# ppc_extbus.net
KiCad netlist of a schematic drawn in Altium Designer
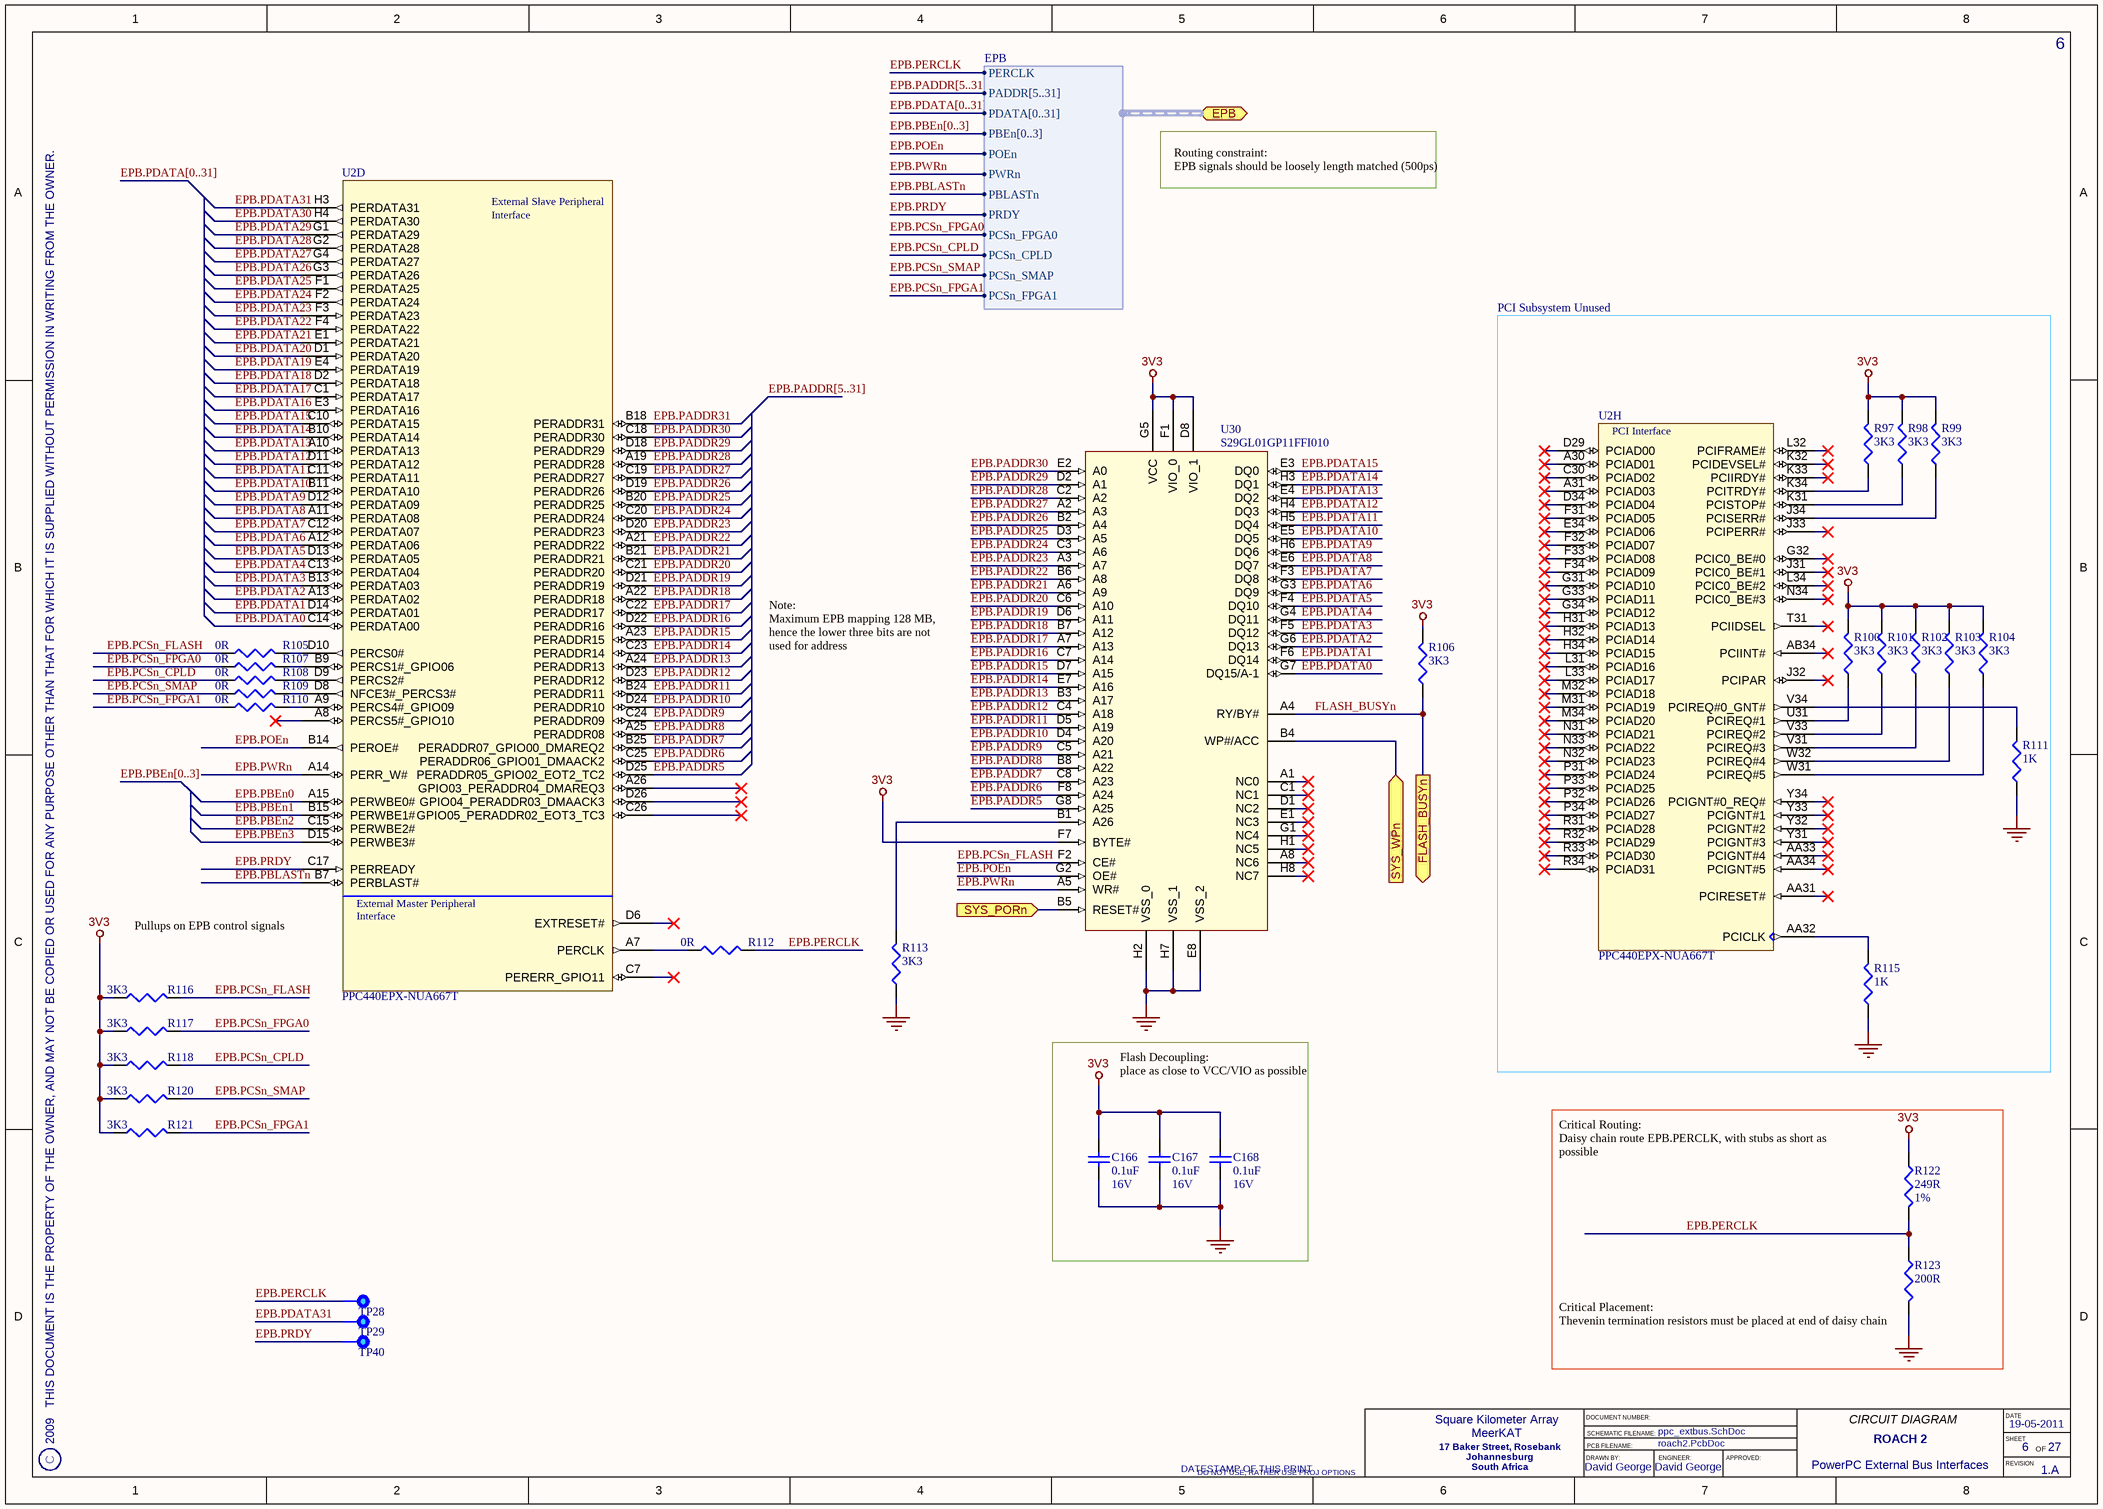
[diagram p0: ppc_extbus.SchDoc]

(export (version "E")
  (design (tool "Eeschema 10.0.6"))
  (components
    (comp (ref "C166")
      (value "0.1uF")
      (footprint "CAPC1005X60L")
      (description "0.1uF, Ceramic Capacitor")
      (fields
        (field (name "MANUFACTURER") "VENKEL")
        (field (name "PARTNUM") "C0402X7R160-104KN")
        (field (name "RATING") "16V")
      )
      (libsource (lib "altium_db") (part "CapStd"))
    )
    (comp (ref "C167")
      (value "0.1uF")
      (footprint "CAPC1005X60L")
      (description "0.1uF, Ceramic Capacitor")
      (fields
        (field (name "MANUFACTURER") "VENKEL")
        (field (name "PARTNUM") "C0402X7R160-104KN")
        (field (name "RATING") "16V")
      )
      (libsource (lib "altium_db") (part "CapStd"))
    )
    (comp (ref "C168")
      (value "0.1uF")
      (footprint "CAPC1005X60L")
      (description "0.1uF, Ceramic Capacitor")
      (fields
        (field (name "MANUFACTURER") "VENKEL")
        (field (name "PARTNUM") "C0402X7R160-104KN")
        (field (name "RATING") "16V")
      )
      (libsource (lib "altium_db") (part "CapStd"))
    )
    (comp (ref "R97")
      (value "3K3")
      (footprint "RESC1005X40L")
      (description "3K3, 1.1mm x 0.5mm, Thick Film Resistor")
      (fields (field (name "MANUFACTURER") "ROYALOHM") (field (name "PARTNUM") "0402WGJ0332T1E"))
      (libsource (lib "altium_db") (part "ResStd"))
    )
    (comp (ref "R98")
      (value "3K3")
      (footprint "RESC1005X40L")
      (description "3K3, 1.1mm x 0.5mm, Thick Film Resistor")
      (fields (field (name "MANUFACTURER") "ROYALOHM") (field (name "PARTNUM") "0402WGJ0332T1E"))
      (libsource (lib "altium_db") (part "ResStd"))
    )
    (comp (ref "R99")
      (value "3K3")
      (footprint "RESC1005X40L")
      (description "3K3, 1.1mm x 0.5mm, Thick Film Resistor")
      (fields (field (name "MANUFACTURER") "ROYALOHM") (field (name "PARTNUM") "0402WGJ0332T1E"))
      (libsource (lib "altium_db") (part "ResStd"))
    )
    (comp (ref "R100")
      (value "3K3")
      (footprint "RESC1005X40L")
      (description "3K3, 1.1mm x 0.5mm, Thick Film Resistor")
      (fields (field (name "MANUFACTURER") "ROYALOHM") (field (name "PARTNUM") "0402WGJ0332T1E"))
      (libsource (lib "altium_db") (part "ResStd"))
    )
    (comp (ref "R101")
      (value "3K3")
      (footprint "RESC1005X40L")
      (description "3K3, 1.1mm x 0.5mm, Thick Film Resistor")
      (fields (field (name "MANUFACTURER") "ROYALOHM") (field (name "PARTNUM") "0402WGJ0332T1E"))
      (libsource (lib "altium_db") (part "ResStd"))
    )
    (comp (ref "R102")
      (value "3K3")
      (footprint "RESC1005X40L")
      (description "3K3, 1.1mm x 0.5mm, Thick Film Resistor")
      (fields (field (name "MANUFACTURER") "ROYALOHM") (field (name "PARTNUM") "0402WGJ0332T1E"))
      (libsource (lib "altium_db") (part "ResStd"))
    )
    (comp (ref "R103")
      (value "3K3")
      (footprint "RESC1005X40L")
      (description "3K3, 1.1mm x 0.5mm, Thick Film Resistor")
      (fields (field (name "MANUFACTURER") "ROYALOHM") (field (name "PARTNUM") "0402WGJ0332T1E"))
      (libsource (lib "altium_db") (part "ResStd"))
    )
    (comp (ref "R104")
      (value "3K3")
      (footprint "RESC1005X40L")
      (description "3K3, 1.1mm x 0.5mm, Thick Film Resistor")
      (fields (field (name "MANUFACTURER") "ROYALOHM") (field (name "PARTNUM") "0402WGJ0332T1E"))
      (libsource (lib "altium_db") (part "ResStd"))
    )
    (comp (ref "R105")
      (value "0R")
      (footprint "RESC1005X40L")
      (description "0R, 1.1mm x 0.5mm, Thick Film Resistor")
      (fields (field (name "MANUFACTURER") "ROYALOHM") (field (name "PARTNUM") "0402WG00000T1E"))
      (libsource (lib "altium_db") (part "ResStd"))
    )
    (comp (ref "R106")
      (value "3K3")
      (footprint "RESC1005X40L")
      (description "3K3, 1.1mm x 0.5mm, Thick Film Resistor")
      (fields (field (name "MANUFACTURER") "ROYALOHM") (field (name "PARTNUM") "0402WGJ0332T1E"))
      (libsource (lib "altium_db") (part "ResStd"))
    )
    (comp (ref "R107")
      (value "0R")
      (footprint "RESC1005X40L")
      (description "0R, 1.1mm x 0.5mm, Thick Film Resistor")
      (fields (field (name "MANUFACTURER") "ROYALOHM") (field (name "PARTNUM") "0402WG00000T1E"))
      (libsource (lib "altium_db") (part "ResStd"))
    )
    (comp (ref "R108")
      (value "0R")
      (footprint "RESC1005X40L")
      (description "0R, 1.1mm x 0.5mm, Thick Film Resistor")
      (fields (field (name "MANUFACTURER") "ROYALOHM") (field (name "PARTNUM") "0402WG00000T1E"))
      (libsource (lib "altium_db") (part "ResStd"))
    )
    (comp (ref "R109")
      (value "0R")
      (footprint "RESC1005X40L")
      (description "0R, 1.1mm x 0.5mm, Thick Film Resistor")
      (fields (field (name "MANUFACTURER") "ROYALOHM") (field (name "PARTNUM") "0402WG00000T1E"))
      (libsource (lib "altium_db") (part "ResStd"))
    )
    (comp (ref "R110")
      (value "0R")
      (footprint "RESC1005X40L")
      (description "0R, 1.1mm x 0.5mm, Thick Film Resistor")
      (fields (field (name "MANUFACTURER") "ROYALOHM") (field (name "PARTNUM") "0402WG00000T1E"))
      (libsource (lib "altium_db") (part "ResStd"))
    )
    (comp (ref "R111")
      (value "1K")
      (footprint "RESC1005X40L")
      (description "1K, 1.1mm x 0.5mm, Thick Film Resistor")
      (fields (field (name "MANUFACTURER") "ROYALOHM") (field (name "PARTNUM") "0402WGJ0102T1E"))
      (libsource (lib "altium_db") (part "ResStd"))
    )
    (comp (ref "R112")
      (value "0R")
      (footprint "RESC1005X40L")
      (description "0R, 1.1mm x 0.5mm, Thick Film Resistor")
      (fields (field (name "MANUFACTURER") "ROYALOHM") (field (name "PARTNUM") "0402WG00000T1E"))
      (libsource (lib "altium_db") (part "ResStd"))
    )
    (comp (ref "R113")
      (value "3K3")
      (footprint "RESC1005X40L")
      (description "3K3, 1.1mm x 0.5mm, Thick Film Resistor")
      (fields (field (name "MANUFACTURER") "ROYALOHM") (field (name "PARTNUM") "0402WGJ0332T1E"))
      (libsource (lib "altium_db") (part "ResStd"))
    )
    (comp (ref "R115")
      (value "1K")
      (footprint "RESC1005X40L")
      (description "1K, 1.1mm x 0.5mm, Thick Film Resistor")
      (fields (field (name "MANUFACTURER") "ROYALOHM") (field (name "PARTNUM") "0402WGJ0102T1E"))
      (libsource (lib "altium_db") (part "ResStd"))
    )
    (comp (ref "R116")
      (value "3K3")
      (footprint "RESC1005X40L")
      (description "3K3, 1.1mm x 0.5mm, Thick Film Resistor")
      (fields (field (name "MANUFACTURER") "ROYALOHM") (field (name "PARTNUM") "0402WGJ0332T1E"))
      (libsource (lib "altium_db") (part "ResStd"))
    )
    (comp (ref "R117")
      (value "3K3")
      (footprint "RESC1005X40L")
      (description "3K3, 1.1mm x 0.5mm, Thick Film Resistor")
      (fields (field (name "MANUFACTURER") "ROYALOHM") (field (name "PARTNUM") "0402WGJ0332T1E"))
      (libsource (lib "altium_db") (part "ResStd"))
    )
    (comp (ref "R118")
      (value "3K3")
      (footprint "RESC1005X40L")
      (description "3K3, 1.1mm x 0.5mm, Thick Film Resistor")
      (fields (field (name "MANUFACTURER") "ROYALOHM") (field (name "PARTNUM") "0402WGJ0332T1E"))
      (libsource (lib "altium_db") (part "ResStd"))
    )
    (comp (ref "R120")
      (value "3K3")
      (footprint "RESC1005X40L")
      (description "3K3, 1.1mm x 0.5mm, Thick Film Resistor")
      (fields (field (name "MANUFACTURER") "ROYALOHM") (field (name "PARTNUM") "0402WGJ0332T1E"))
      (libsource (lib "altium_db") (part "ResStd"))
    )
    (comp (ref "R121")
      (value "3K3")
      (footprint "RESC1005X40L")
      (description "3K3, 1.1mm x 0.5mm, Thick Film Resistor")
      (fields (field (name "MANUFACTURER") "ROYALOHM") (field (name "PARTNUM") "0402WGJ0332T1E"))
      (libsource (lib "altium_db") (part "ResStd"))
    )
    (comp (ref "R122")
      (value "249R")
      (footprint "RESC1005X40L")
      (description "249R, 1.1mm x 0.5mm, Thick Film Resistor")
      (fields
        (field (name "MANUFACTURER") "ROYALOHM")
        (field (name "PARTNUM") "0402WGF2490T1E")
        (field (name "TOLERANCE") "1%")
      )
      (libsource (lib "altium_db") (part "ResStd"))
    )
    (comp (ref "R123")
      (value "200R")
      (footprint "RESC1005X40L")
      (description "200R, 1.1mm x 0.5mm, Thick Film Resistor")
      (fields (field (name "MANUFACTURER") "ROYALOHM") (field (name "PARTNUM") "0402WGF0201T1E"))
      (libsource (lib "altium_db") (part "ResStd"))
    )
    (comp (ref "TP28")
      (value "Testpoint")
      (footprint "TP100")
      (description "1mm Diameter, through-hole, Circular Test-point")
      (libsource (lib "altium_db") (part "Testpoint"))
    )
    (comp (ref "TP29")
      (value "Testpoint")
      (footprint "TP100")
      (description "1mm Diameter, through-hole, Circular Test-point")
      (libsource (lib "altium_db") (part "Testpoint"))
    )
    (comp (ref "TP40")
      (value "Testpoint")
      (footprint "TP100")
      (description "1mm Diameter, through-hole, Circular Test-point")
      (libsource (lib "altium_db") (part "Testpoint"))
    )
    (comp (ref "U2")
      (value "PPC440EPX-NUA667T")
      (footprint "TE-PBGA680")
      (description "667MHz, non-RoHS, PPC440EPx uProcessor")
      (fields (field (name "MANUFACTURER") "Applied Micro"))
      (libsource (lib "altium_db") (part "PPC440EPX"))
    )
    (comp (ref "U30")
      (value "S29GL01GP11FFI010")
      (footprint "LAA064")
      (description "3V, 1 Gigabit NOR Flash")
      (fields (field (name "MANUFACTURER") "Spansion"))
      (libsource (lib "altium_db") (part "S29GL01GP"))
    )
  )
  (nets
    (net (code "2") (name "/EPB.PADDR5") (class "Default")
      (node (ref "U2") (pin "D25") (pinfunction "PERADDR05_GPIO02_EOT2_TC2_D25") (pintype "bidirectional"))
      (node (ref "U30") (pin "G8") (pinfunction "A25_G8") (pintype "input"))
    )
    (net (code "3") (name "/EPB.PADDR6") (class "Default")
      (node (ref "U2") (pin "C25") (pinfunction "PERADDR06_GPIO01_DMAACK2_C25") (pintype "bidirectional"))
      (node (ref "U30") (pin "F8") (pinfunction "A24_F8") (pintype "input"))
    )
    (net (code "4") (name "/EPB.PADDR7") (class "Default")
      (node (ref "U2") (pin "B25") (pinfunction "PERADDR07_GPIO00_DMAREQ2_B25") (pintype "bidirectional"))
      (node (ref "U30") (pin "C8") (pinfunction "A23_C8") (pintype "input"))
    )
    (net (code "5") (name "/EPB.PADDR8") (class "Default")
      (node (ref "U2") (pin "A25") (pinfunction "PERADDR08_A25") (pintype "bidirectional"))
      (node (ref "U30") (pin "B8") (pinfunction "A22_B8") (pintype "input"))
    )
    (net (code "6") (name "/EPB.PADDR9") (class "Default")
      (node (ref "U2") (pin "C24") (pinfunction "PERADDR09_C24") (pintype "bidirectional"))
      (node (ref "U30") (pin "C5") (pinfunction "A21_C5") (pintype "input"))
    )
    (net (code "7") (name "/EPB.PADDR10") (class "Default")
      (node (ref "U2") (pin "D24") (pinfunction "PERADDR10_D24") (pintype "bidirectional"))
      (node (ref "U30") (pin "D4") (pinfunction "A20_D4") (pintype "input"))
    )
    (net (code "8") (name "/EPB.PADDR11") (class "Default")
      (node (ref "U2") (pin "B24") (pinfunction "PERADDR11_B24") (pintype "bidirectional"))
      (node (ref "U30") (pin "D5") (pinfunction "A19_D5") (pintype "input"))
    )
    (net (code "9") (name "/EPB.PADDR12") (class "Default")
      (node (ref "U2") (pin "D23") (pinfunction "PERADDR12_D23") (pintype "bidirectional"))
      (node (ref "U30") (pin "C4") (pinfunction "A18_C4") (pintype "input"))
    )
    (net (code "10") (name "/EPB.PADDR13") (class "Default")
      (node (ref "U2") (pin "A24") (pinfunction "PERADDR13_A24") (pintype "bidirectional"))
      (node (ref "U30") (pin "B3") (pinfunction "A17_B3") (pintype "input"))
    )
    (net (code "11") (name "/EPB.PADDR14") (class "Default")
      (node (ref "U2") (pin "C23") (pinfunction "PERADDR14_C23") (pintype "bidirectional"))
      (node (ref "U30") (pin "E7") (pinfunction "A16_E7") (pintype "input"))
    )
    (net (code "12") (name "/EPB.PADDR15") (class "Default")
      (node (ref "U2") (pin "A23") (pinfunction "PERADDR15_A23") (pintype "bidirectional"))
      (node (ref "U30") (pin "D7") (pinfunction "A15_D7") (pintype "input"))
    )
    (net (code "13") (name "/EPB.PADDR16") (class "Default")
      (node (ref "U2") (pin "D22") (pinfunction "PERADDR16_D22") (pintype "bidirectional"))
      (node (ref "U30") (pin "C7") (pinfunction "A14_C7") (pintype "input"))
    )
    (net (code "14") (name "/EPB.PADDR17") (class "Default")
      (node (ref "U2") (pin "C22") (pinfunction "PERADDR17_C22") (pintype "bidirectional"))
      (node (ref "U30") (pin "A7") (pinfunction "A13_A7") (pintype "input"))
    )
    (net (code "15") (name "/EPB.PADDR18") (class "Default")
      (node (ref "U2") (pin "A22") (pinfunction "PERADDR18_A22") (pintype "bidirectional"))
      (node (ref "U30") (pin "B7") (pinfunction "A12_B7") (pintype "input"))
    )
    (net (code "16") (name "/EPB.PADDR19") (class "Default")
      (node (ref "U2") (pin "D21") (pinfunction "PERADDR19_D21") (pintype "bidirectional"))
      (node (ref "U30") (pin "D6") (pinfunction "A11_D6") (pintype "input"))
    )
    (net (code "17") (name "/EPB.PADDR20") (class "Default")
      (node (ref "U2") (pin "C21") (pinfunction "PERADDR20_C21") (pintype "bidirectional"))
      (node (ref "U30") (pin "C6") (pinfunction "A10_C6") (pintype "input"))
    )
    (net (code "18") (name "/EPB.PADDR21") (class "Default")
      (node (ref "U2") (pin "B21") (pinfunction "PERADDR21_B21") (pintype "bidirectional"))
      (node (ref "U30") (pin "A6") (pinfunction "A9_A6") (pintype "input"))
    )
    (net (code "19") (name "/EPB.PADDR22") (class "Default")
      (node (ref "U2") (pin "A21") (pinfunction "PERADDR22_A21") (pintype "bidirectional"))
      (node (ref "U30") (pin "B6") (pinfunction "A8_B6") (pintype "input"))
    )
    (net (code "20") (name "/EPB.PADDR23") (class "Default")
      (node (ref "U2") (pin "D20") (pinfunction "PERADDR23_D20") (pintype "bidirectional"))
      (node (ref "U30") (pin "A3") (pinfunction "A7_A3") (pintype "input"))
    )
    (net (code "21") (name "/EPB.PADDR24") (class "Default")
      (node (ref "U2") (pin "C20") (pinfunction "PERADDR24_C20") (pintype "bidirectional"))
      (node (ref "U30") (pin "C3") (pinfunction "A6_C3") (pintype "input"))
    )
    (net (code "22") (name "/EPB.PADDR25") (class "Default")
      (node (ref "U2") (pin "B20") (pinfunction "PERADDR25_B20") (pintype "bidirectional"))
      (node (ref "U30") (pin "D3") (pinfunction "A5_D3") (pintype "input"))
    )
    (net (code "23") (name "/EPB.PADDR26") (class "Default")
      (node (ref "U2") (pin "D19") (pinfunction "PERADDR26_D19") (pintype "bidirectional"))
      (node (ref "U30") (pin "B2") (pinfunction "A4_B2") (pintype "input"))
    )
    (net (code "24") (name "/EPB.PADDR27") (class "Default")
      (node (ref "U2") (pin "C19") (pinfunction "PERADDR27_C19") (pintype "bidirectional"))
      (node (ref "U30") (pin "A2") (pinfunction "A3_A2") (pintype "input"))
    )
    (net (code "25") (name "/EPB.PADDR28") (class "Default")
      (node (ref "U2") (pin "A19") (pinfunction "PERADDR28_A19") (pintype "bidirectional"))
      (node (ref "U30") (pin "C2") (pinfunction "A2_C2") (pintype "input"))
    )
    (net (code "26") (name "/EPB.PADDR29") (class "Default")
      (node (ref "U2") (pin "D18") (pinfunction "PERADDR29_D18") (pintype "bidirectional"))
      (node (ref "U30") (pin "D2") (pinfunction "A1_D2") (pintype "input"))
    )
    (net (code "27") (name "/EPB.PADDR30") (class "Default")
      (node (ref "U2") (pin "C18") (pinfunction "PERADDR30_C18") (pintype "bidirectional"))
      (node (ref "U30") (pin "E2") (pinfunction "A0_E2") (pintype "input"))
    )
    (net (code "28") (name "/EPB.PADDR31") (class "Default")
      (node (ref "U2") (pin "B18") (pinfunction "PERADDR31_B18") (pintype "bidirectional"))
    )
    (net (code "30") (name "/EPB.PBEn0") (class "Default")
      (node (ref "U2") (pin "A15") (pinfunction "PERWBE0#_A15") (pintype "bidirectional"))
    )
    (net (code "31") (name "/EPB.PBEn1") (class "Default")
      (node (ref "U2") (pin "B15") (pinfunction "PERWBE1#_B15") (pintype "bidirectional"))
    )
    (net (code "32") (name "/EPB.PBEn2") (class "Default")
      (node (ref "U2") (pin "C15") (pinfunction "PERWBE2#_C15") (pintype "bidirectional"))
    )
    (net (code "33") (name "/EPB.PBEn3") (class "Default")
      (node (ref "U2") (pin "D15") (pinfunction "PERWBE3#_D15") (pintype "bidirectional"))
    )
    (net (code "35") (name "/EPB.PBLASTn") (class "Default")
      (node (ref "U2") (pin "B7") (pinfunction "PERBLAST#_B7") (pintype "bidirectional"))
    )
    (net (code "36") (name "/EPB.PCSn_CPLD") (class "Default")
      (node (ref "R108") (pin "1") (pinfunction "1_1") (pintype "passive"))
      (node (ref "R118") (pin "2") (pinfunction "2_2") (pintype "passive"))
    )
    (net (code "37") (name "/EPB.PCSn_FLASH") (class "Default")
      (node (ref "R105") (pin "1") (pinfunction "1_1") (pintype "passive"))
      (node (ref "R116") (pin "2") (pinfunction "2_2") (pintype "passive"))
      (node (ref "U30") (pin "F2") (pinfunction "CE#_F2") (pintype "input"))
    )
    (net (code "38") (name "/EPB.PCSn_FPGA0") (class "Default")
      (node (ref "R107") (pin "1") (pinfunction "1_1") (pintype "passive"))
      (node (ref "R117") (pin "2") (pinfunction "2_2") (pintype "passive"))
    )
    (net (code "39") (name "/EPB.PCSn_FPGA1") (class "Default")
      (node (ref "R110") (pin "1") (pinfunction "1_1") (pintype "passive"))
      (node (ref "R121") (pin "2") (pinfunction "2_2") (pintype "passive"))
    )
    (net (code "40") (name "/EPB.PCSn_SMAP") (class "Default")
      (node (ref "R109") (pin "1") (pinfunction "1_1") (pintype "passive"))
      (node (ref "R120") (pin "2") (pinfunction "2_2") (pintype "passive"))
    )
    (net (code "41") (name "/EPB.PDATA0") (class "Default")
      (node (ref "U2") (pin "C14") (pinfunction "PERDATA00_C14") (pintype "bidirectional"))
      (node (ref "U30") (pin "G7") (pinfunction "DQ15/A-1_G7") (pintype "bidirectional"))
    )
    (net (code "42") (name "/EPB.PDATA1") (class "Default")
      (node (ref "U2") (pin "D14") (pinfunction "PERDATA01_D14") (pintype "bidirectional"))
      (node (ref "U30") (pin "F6") (pinfunction "DQ14_F6") (pintype "bidirectional"))
    )
    (net (code "43") (name "/EPB.PDATA2") (class "Default")
      (node (ref "U2") (pin "A13") (pinfunction "PERDATA02_A13") (pintype "bidirectional"))
      (node (ref "U30") (pin "G6") (pinfunction "DQ13_G6") (pintype "bidirectional"))
    )
    (net (code "44") (name "/EPB.PDATA3") (class "Default")
      (node (ref "U2") (pin "B13") (pinfunction "PERDATA03_B13") (pintype "bidirectional"))
      (node (ref "U30") (pin "F5") (pinfunction "DQ12_F5") (pintype "bidirectional"))
    )
    (net (code "45") (name "/EPB.PDATA4") (class "Default")
      (node (ref "U2") (pin "C13") (pinfunction "PERDATA04_C13") (pintype "bidirectional"))
      (node (ref "U30") (pin "G4") (pinfunction "DQ11_G4") (pintype "bidirectional"))
    )
    (net (code "46") (name "/EPB.PDATA5") (class "Default")
      (node (ref "U2") (pin "D13") (pinfunction "PERDATA05_D13") (pintype "bidirectional"))
      (node (ref "U30") (pin "F4") (pinfunction "DQ10_F4") (pintype "bidirectional"))
    )
    (net (code "47") (name "/EPB.PDATA6") (class "Default")
      (node (ref "U2") (pin "A12") (pinfunction "PERDATA06_A12") (pintype "bidirectional"))
      (node (ref "U30") (pin "G3") (pinfunction "DQ9_G3") (pintype "bidirectional"))
    )
    (net (code "48") (name "/EPB.PDATA7") (class "Default")
      (node (ref "U2") (pin "C12") (pinfunction "PERDATA07_C12") (pintype "bidirectional"))
      (node (ref "U30") (pin "F3") (pinfunction "DQ8_F3") (pintype "bidirectional"))
    )
    (net (code "49") (name "/EPB.PDATA8") (class "Default")
      (node (ref "U2") (pin "A11") (pinfunction "PERDATA08_A11") (pintype "bidirectional"))
      (node (ref "U30") (pin "E6") (pinfunction "DQ7_E6") (pintype "bidirectional"))
    )
    (net (code "50") (name "/EPB.PDATA9") (class "Default")
      (node (ref "U2") (pin "D12") (pinfunction "PERDATA09_D12") (pintype "bidirectional"))
      (node (ref "U30") (pin "H6") (pinfunction "DQ6_H6") (pintype "bidirectional"))
    )
    (net (code "51") (name "/EPB.PDATA10") (class "Default")
      (node (ref "U2") (pin "B11") (pinfunction "PERDATA10_B11") (pintype "bidirectional"))
      (node (ref "U30") (pin "E5") (pinfunction "DQ5_E5") (pintype "bidirectional"))
    )
    (net (code "52") (name "/EPB.PDATA11") (class "Default")
      (node (ref "U2") (pin "C11") (pinfunction "PERDATA11_C11") (pintype "bidirectional"))
      (node (ref "U30") (pin "H5") (pinfunction "DQ4_H5") (pintype "bidirectional"))
    )
    (net (code "53") (name "/EPB.PDATA12") (class "Default")
      (node (ref "U2") (pin "D11") (pinfunction "PERDATA12_D11") (pintype "bidirectional"))
      (node (ref "U30") (pin "H4") (pinfunction "DQ3_H4") (pintype "bidirectional"))
    )
    (net (code "54") (name "/EPB.PDATA13") (class "Default")
      (node (ref "U2") (pin "A10") (pinfunction "PERDATA13_A10") (pintype "bidirectional"))
      (node (ref "U30") (pin "E4") (pinfunction "DQ2_E4") (pintype "bidirectional"))
    )
    (net (code "55") (name "/EPB.PDATA14") (class "Default")
      (node (ref "U2") (pin "B10") (pinfunction "PERDATA14_B10") (pintype "bidirectional"))
      (node (ref "U30") (pin "H3") (pinfunction "DQ1_H3") (pintype "bidirectional"))
    )
    (net (code "56") (name "/EPB.PDATA15") (class "Default")
      (node (ref "U2") (pin "C10") (pinfunction "PERDATA15_C10") (pintype "bidirectional"))
      (node (ref "U30") (pin "E3") (pinfunction "DQ0_E3") (pintype "bidirectional"))
    )
    (net (code "57") (name "/EPB.PDATA16") (class "Default")
      (node (ref "U2") (pin "E3") (pinfunction "PERDATA16_E3") (pintype "input"))
    )
    (net (code "58") (name "/EPB.PDATA17") (class "Default")
      (node (ref "U2") (pin "C1") (pinfunction "PERDATA17_C1") (pintype "input"))
    )
    (net (code "59") (name "/EPB.PDATA18") (class "Default")
      (node (ref "U2") (pin "D2") (pinfunction "PERDATA18_D2") (pintype "input"))
    )
    (net (code "60") (name "/EPB.PDATA19") (class "Default")
      (node (ref "U2") (pin "E4") (pinfunction "PERDATA19_E4") (pintype "input"))
    )
    (net (code "61") (name "/EPB.PDATA20") (class "Default")
      (node (ref "U2") (pin "D1") (pinfunction "PERDATA20_D1") (pintype "input"))
    )
    (net (code "62") (name "/EPB.PDATA21") (class "Default")
      (node (ref "U2") (pin "E1") (pinfunction "PERDATA21_E1") (pintype "input"))
    )
    (net (code "63") (name "/EPB.PDATA22") (class "Default")
      (node (ref "U2") (pin "F4") (pinfunction "PERDATA22_F4") (pintype "input"))
    )
    (net (code "64") (name "/EPB.PDATA23") (class "Default")
      (node (ref "U2") (pin "F3") (pinfunction "PERDATA23_F3") (pintype "input"))
    )
    (net (code "65") (name "/EPB.PDATA24") (class "Default")
      (node (ref "U2") (pin "F2") (pinfunction "PERDATA24_F2") (pintype "output"))
    )
    (net (code "66") (name "/EPB.PDATA25") (class "Default")
      (node (ref "U2") (pin "F1") (pinfunction "PERDATA25_F1") (pintype "output"))
    )
    (net (code "67") (name "/EPB.PDATA26") (class "Default")
      (node (ref "U2") (pin "G3") (pinfunction "PERDATA26_G3") (pintype "output"))
    )
    (net (code "68") (name "/EPB.PDATA27") (class "Default")
      (node (ref "U2") (pin "G4") (pinfunction "PERDATA27_G4") (pintype "output"))
    )
    (net (code "69") (name "/EPB.PDATA28") (class "Default")
      (node (ref "U2") (pin "G2") (pinfunction "PERDATA28_G2") (pintype "output"))
    )
    (net (code "70") (name "/EPB.PDATA29") (class "Default")
      (node (ref "U2") (pin "G1") (pinfunction "PERDATA29_G1") (pintype "output"))
    )
    (net (code "71") (name "/EPB.PDATA30") (class "Default")
      (node (ref "U2") (pin "H4") (pinfunction "PERDATA30_H4") (pintype "output"))
    )
    (net (code "72") (name "/EPB.PDATA31") (class "Default")
      (node (ref "TP29") (pin "1") (pinfunction "1_1") (pintype "passive"))
      (node (ref "U2") (pin "H3") (pinfunction "PERDATA31_H3") (pintype "output"))
    )
    (net (code "74") (name "/EPB.PERCLK") (class "Default")
      (node (ref "R112") (pin "2") (pinfunction "2_2") (pintype "passive"))
      (node (ref "R122") (pin "2") (pinfunction "2_2") (pintype "passive"))
      (node (ref "R123") (pin "1") (pinfunction "1_1") (pintype "passive"))
      (node (ref "TP28") (pin "1") (pinfunction "1_1") (pintype "passive"))
    )
    (net (code "75") (name "/EPB.POEn") (class "Default")
      (node (ref "U2") (pin "B14") (pinfunction "PEROE#_B14") (pintype "output"))
      (node (ref "U30") (pin "G2") (pinfunction "OE#_G2") (pintype "input"))
    )
    (net (code "76") (name "/EPB.PRDY") (class "Default")
      (node (ref "TP40") (pin "1") (pinfunction "1_1") (pintype "passive"))
      (node (ref "U2") (pin "C17") (pinfunction "PERREADY_C17") (pintype "input"))
    )
    (net (code "77") (name "/EPB.PWRn") (class "Default")
      (node (ref "U2") (pin "A14") (pinfunction "PERR_W#_A14") (pintype "bidirectional"))
      (node (ref "U30") (pin "A5") (pinfunction "WR#_A5") (pintype "input"))
    )
    (net (code "79") (name "/FLASH_BUSYn") (class "Default")
      (node (ref "R106") (pin "1") (pinfunction "1_1") (pintype "passive"))
      (node (ref "U30") (pin "A4") (pinfunction "RY/BY#_A4") (pintype "open_collector"))
    )
    (net (code "80") (name "/SYS_PORn") (class "Default")
      (node (ref "U30") (pin "B5") (pinfunction "RESET#_B5") (pintype "input"))
    )
    (net (code "81") (name "/SYS_WPn") (class "Default")
      (node (ref "U30") (pin "B4") (pinfunction "WP#/ACC_B4") (pintype "open_collector"))
    )
    (net (code "83") (name "3V3") (class "Default")
      (node (ref "C166") (pin "2") (pinfunction "2_2") (pintype "passive"))
      (node (ref "C167") (pin "2") (pinfunction "2_2") (pintype "passive"))
      (node (ref "C168") (pin "2") (pinfunction "2_2") (pintype "passive"))
      (node (ref "R100") (pin "2") (pinfunction "2_2") (pintype "passive"))
      (node (ref "R101") (pin "2") (pinfunction "2_2") (pintype "passive"))
      (node (ref "R102") (pin "2") (pinfunction "2_2") (pintype "passive"))
      (node (ref "R103") (pin "2") (pinfunction "2_2") (pintype "passive"))
      (node (ref "R104") (pin "2") (pinfunction "2_2") (pintype "passive"))
      (node (ref "R106") (pin "2") (pinfunction "2_2") (pintype "passive"))
      (node (ref "R116") (pin "1") (pinfunction "1_1") (pintype "passive"))
      (node (ref "R117") (pin "1") (pinfunction "1_1") (pintype "passive"))
      (node (ref "R118") (pin "1") (pinfunction "1_1") (pintype "passive"))
      (node (ref "R120") (pin "1") (pinfunction "1_1") (pintype "passive"))
      (node (ref "R121") (pin "1") (pinfunction "1_1") (pintype "passive"))
      (node (ref "R122") (pin "1") (pinfunction "1_1") (pintype "passive"))
      (node (ref "R97") (pin "2") (pinfunction "2_2") (pintype "passive"))
      (node (ref "R98") (pin "2") (pinfunction "2_2") (pintype "passive"))
      (node (ref "R99") (pin "2") (pinfunction "2_2") (pintype "passive"))
      (node (ref "U30") (pin "D8") (pinfunction "VIO_1_D8") (pintype "passive"))
      (node (ref "U30") (pin "F1") (pinfunction "VIO_0_F1") (pintype "passive"))
      (node (ref "U30") (pin "F7") (pinfunction "BYTE#_F7") (pintype "input"))
      (node (ref "U30") (pin "G5") (pinfunction "VCC_G5") (pintype "passive"))
    )
    (net (code "84") (name "GND") (class "Default")
      (node (ref "C166") (pin "1") (pinfunction "1_1") (pintype "passive"))
      (node (ref "C167") (pin "1") (pinfunction "1_1") (pintype "passive"))
      (node (ref "C168") (pin "1") (pinfunction "1_1") (pintype "passive"))
      (node (ref "R111") (pin "1") (pinfunction "1_1") (pintype "passive"))
      (node (ref "R113") (pin "1") (pinfunction "1_1") (pintype "passive"))
      (node (ref "R115") (pin "1") (pinfunction "1_1") (pintype "passive"))
      (node (ref "R123") (pin "2") (pinfunction "2_2") (pintype "passive"))
      (node (ref "U30") (pin "E8") (pinfunction "VSS_2_E8") (pintype "passive"))
      (node (ref "U30") (pin "H2") (pinfunction "VSS_0_H2") (pintype "passive"))
      (node (ref "U30") (pin "H7") (pinfunction "VSS_1_H7") (pintype "passive"))
    )
    (net (code "85") (name "Net-(U2D-NFCE3#_PERCS3#)") (class "Default")
      (node (ref "R109") (pin "2") (pinfunction "2_2") (pintype "passive"))
      (node (ref "U2") (pin "D8") (pinfunction "NFCE3#_PERCS3#_D8") (pintype "output"))
    )
    (net (code "86") (name "Net-(U2D-PERCLK)") (class "Default")
      (node (ref "R112") (pin "1") (pinfunction "1_1") (pintype "passive"))
      (node (ref "U2") (pin "A7") (pinfunction "PERCLK_A7") (pintype "output"))
    )
    (net (code "87") (name "Net-(U2D-PERCS0#)") (class "Default")
      (node (ref "R105") (pin "2") (pinfunction "2_2") (pintype "passive"))
      (node (ref "U2") (pin "D10") (pinfunction "PERCS0#_D10") (pintype "output"))
    )
    (net (code "88") (name "Net-(U2D-PERCS1#_GPIO06)") (class "Default")
      (node (ref "R107") (pin "2") (pinfunction "2_2") (pintype "passive"))
      (node (ref "U2") (pin "B9") (pinfunction "PERCS1#_GPIO06_B9") (pintype "bidirectional"))
    )
    (net (code "89") (name "Net-(U2D-PERCS2#)") (class "Default")
      (node (ref "R108") (pin "2") (pinfunction "2_2") (pintype "passive"))
      (node (ref "U2") (pin "D9") (pinfunction "PERCS2#_D9") (pintype "output"))
    )
    (net (code "90") (name "Net-(U2D-PERCS4#_GPIO09)") (class "Default")
      (node (ref "R110") (pin "2") (pinfunction "2_2") (pintype "passive"))
      (node (ref "U2") (pin "A9") (pinfunction "PERCS4#_GPIO09_A9") (pintype "bidirectional"))
    )
    (net (code "91") (name "Net-(U2H-PCICLK)") (class "Default")
      (node (ref "R115") (pin "2") (pinfunction "2_2") (pintype "passive"))
      (node (ref "U2") (pin "AA32") (pinfunction "PCICLK_AA32") (pintype "output"))
    )
    (net (code "92") (name "Net-(U2H-PCIREQ#0_GNT#)") (class "Default")
      (node (ref "R111") (pin "2") (pinfunction "2_2") (pintype "passive"))
      (node (ref "U2") (pin "V34") (pinfunction "PCIREQ#0_GNT#_V34") (pintype "output"))
    )
    (net (code "93") (name "Net-(U2H-PCIREQ#1)") (class "Default")
      (node (ref "R100") (pin "1") (pinfunction "1_1") (pintype "passive"))
      (node (ref "U2") (pin "U31") (pinfunction "PCIREQ#1_U31") (pintype "output"))
    )
    (net (code "94") (name "Net-(U2H-PCIREQ#2)") (class "Default")
      (node (ref "R101") (pin "1") (pinfunction "1_1") (pintype "passive"))
      (node (ref "U2") (pin "V33") (pinfunction "PCIREQ#2_V33") (pintype "output"))
    )
    (net (code "95") (name "Net-(U2H-PCIREQ#3)") (class "Default")
      (node (ref "R102") (pin "1") (pinfunction "1_1") (pintype "passive"))
      (node (ref "U2") (pin "V31") (pinfunction "PCIREQ#3_V31") (pintype "output"))
    )
    (net (code "96") (name "Net-(U2H-PCIREQ#4)") (class "Default")
      (node (ref "R103") (pin "1") (pinfunction "1_1") (pintype "passive"))
      (node (ref "U2") (pin "W32") (pinfunction "PCIREQ#4_W32") (pintype "output"))
    )
    (net (code "97") (name "Net-(U2H-PCIREQ#5)") (class "Default")
      (node (ref "R104") (pin "1") (pinfunction "1_1") (pintype "passive"))
      (node (ref "U2") (pin "W31") (pinfunction "PCIREQ#5_W31") (pintype "output"))
    )
    (net (code "98") (name "Net-(U2H-PCISERR#)") (class "Default")
      (node (ref "R99") (pin "1") (pinfunction "1_1") (pintype "passive"))
      (node (ref "U2") (pin "J34") (pinfunction "PCISERR#_J34") (pintype "bidirectional"))
    )
    (net (code "99") (name "Net-(U2H-PCISTOP#)") (class "Default")
      (node (ref "R98") (pin "1") (pinfunction "1_1") (pintype "passive"))
      (node (ref "U2") (pin "K31") (pinfunction "PCISTOP#_K31") (pintype "bidirectional"))
    )
    (net (code "100") (name "Net-(U2H-PCITRDY#)") (class "Default")
      (node (ref "R97") (pin "1") (pinfunction "1_1") (pintype "passive"))
      (node (ref "U2") (pin "K34") (pinfunction "PCITRDY#_K34") (pintype "bidirectional"))
    )
    (net (code "101") (name "Net-(U30-A26)") (class "Default")
      (node (ref "R113") (pin "2") (pinfunction "2_2") (pintype "passive"))
      (node (ref "U30") (pin "B1") (pinfunction "A26_B1") (pintype "input"))
    )
    (net (code "102") (name "unconnected-(U2D-EXTRESET#-PadD6)") (class "Default")
      (node (ref "U2") (pin "D6") (pinfunction "EXTRESET#_D6") (pintype "output+no_connect"))
    )
    (net (code "103") (name "unconnected-(U2D-GPIO03_PERADDR04_DMAREQ3-PadA26)") (class "Default")
      (node (ref "U2") (pin "A26") (pinfunction "GPIO03_PERADDR04_DMAREQ3_A26") (pintype "bidirectional+no_connect"))
    )
    (net (code "104") (name "unconnected-(U2D-GPIO04_PERADDR03_DMAACK3-PadD26)") (class "Default")
      (node (ref "U2") (pin "D26") (pinfunction "GPIO04_PERADDR03_DMAACK3_D26") (pintype "bidirectional+no_connect"))
    )
    (net (code "105") (name "unconnected-(U2D-GPIO05_PERADDR02_EOT3_TC3-PadC26)") (class "Default")
      (node (ref "U2") (pin "C26") (pinfunction "GPIO05_PERADDR02_EOT3_TC3_C26") (pintype "bidirectional+no_connect"))
    )
    (net (code "106") (name "unconnected-(U2D-PERCS5#_GPIO10-PadA8)") (class "Default")
      (node (ref "U2") (pin "A8") (pinfunction "PERCS5#_GPIO10_A8") (pintype "bidirectional+no_connect"))
    )
    (net (code "107") (name "unconnected-(U2D-PERERR_GPIO11-PadC7)") (class "Default")
      (node (ref "U2") (pin "C7") (pinfunction "PERERR_GPIO11_C7") (pintype "bidirectional+no_connect"))
    )
    (net (code "108") (name "unconnected-(U2H-PCIAD00-PadD29)") (class "Default")
      (node (ref "U2") (pin "D29") (pinfunction "PCIAD00_D29") (pintype "bidirectional+no_connect"))
    )
    (net (code "109") (name "unconnected-(U2H-PCIAD01-PadA30)") (class "Default")
      (node (ref "U2") (pin "A30") (pinfunction "PCIAD01_A30") (pintype "bidirectional+no_connect"))
    )
    (net (code "110") (name "unconnected-(U2H-PCIAD02-PadC30)") (class "Default")
      (node (ref "U2") (pin "C30") (pinfunction "PCIAD02_C30") (pintype "bidirectional+no_connect"))
    )
    (net (code "111") (name "unconnected-(U2H-PCIAD03-PadA31)") (class "Default")
      (node (ref "U2") (pin "A31") (pinfunction "PCIAD03_A31") (pintype "bidirectional+no_connect"))
    )
    (net (code "112") (name "unconnected-(U2H-PCIAD04-PadD34)") (class "Default")
      (node (ref "U2") (pin "D34") (pinfunction "PCIAD04_D34") (pintype "bidirectional+no_connect"))
    )
    (net (code "113") (name "unconnected-(U2H-PCIAD05-PadF31)") (class "Default")
      (node (ref "U2") (pin "F31") (pinfunction "PCIAD05_F31") (pintype "bidirectional+no_connect"))
    )
    (net (code "114") (name "unconnected-(U2H-PCIAD06-PadE34)") (class "Default")
      (node (ref "U2") (pin "E34") (pinfunction "PCIAD06_E34") (pintype "bidirectional+no_connect"))
    )
    (net (code "115") (name "unconnected-(U2H-PCIAD07-PadF32)") (class "Default")
      (node (ref "U2") (pin "F32") (pinfunction "PCIAD07_F32") (pintype "bidirectional+no_connect"))
    )
    (net (code "116") (name "unconnected-(U2H-PCIAD08-PadF33)") (class "Default")
      (node (ref "U2") (pin "F33") (pinfunction "PCIAD08_F33") (pintype "bidirectional+no_connect"))
    )
    (net (code "117") (name "unconnected-(U2H-PCIAD09-PadF34)") (class "Default")
      (node (ref "U2") (pin "F34") (pinfunction "PCIAD09_F34") (pintype "bidirectional+no_connect"))
    )
    (net (code "118") (name "unconnected-(U2H-PCIAD10-PadG31)") (class "Default")
      (node (ref "U2") (pin "G31") (pinfunction "PCIAD10_G31") (pintype "bidirectional+no_connect"))
    )
    (net (code "119") (name "unconnected-(U2H-PCIAD11-PadG33)") (class "Default")
      (node (ref "U2") (pin "G33") (pinfunction "PCIAD11_G33") (pintype "bidirectional+no_connect"))
    )
    (net (code "120") (name "unconnected-(U2H-PCIAD12-PadG34)") (class "Default")
      (node (ref "U2") (pin "G34") (pinfunction "PCIAD12_G34") (pintype "bidirectional+no_connect"))
    )
    (net (code "121") (name "unconnected-(U2H-PCIAD13-PadH31)") (class "Default")
      (node (ref "U2") (pin "H31") (pinfunction "PCIAD13_H31") (pintype "bidirectional+no_connect"))
    )
    (net (code "122") (name "unconnected-(U2H-PCIAD14-PadH32)") (class "Default")
      (node (ref "U2") (pin "H32") (pinfunction "PCIAD14_H32") (pintype "bidirectional+no_connect"))
    )
    (net (code "123") (name "unconnected-(U2H-PCIAD15-PadH34)") (class "Default")
      (node (ref "U2") (pin "H34") (pinfunction "PCIAD15_H34") (pintype "bidirectional+no_connect"))
    )
    (net (code "124") (name "unconnected-(U2H-PCIAD16-PadL31)") (class "Default")
      (node (ref "U2") (pin "L31") (pinfunction "PCIAD16_L31") (pintype "bidirectional+no_connect"))
    )
    (net (code "125") (name "unconnected-(U2H-PCIAD17-PadL33)") (class "Default")
      (node (ref "U2") (pin "L33") (pinfunction "PCIAD17_L33") (pintype "bidirectional+no_connect"))
    )
    (net (code "126") (name "unconnected-(U2H-PCIAD18-PadM32)") (class "Default")
      (node (ref "U2") (pin "M32") (pinfunction "PCIAD18_M32") (pintype "bidirectional+no_connect"))
    )
    (net (code "127") (name "unconnected-(U2H-PCIAD19-PadM31)") (class "Default")
      (node (ref "U2") (pin "M31") (pinfunction "PCIAD19_M31") (pintype "bidirectional+no_connect"))
    )
    (net (code "128") (name "unconnected-(U2H-PCIAD20-PadM34)") (class "Default")
      (node (ref "U2") (pin "M34") (pinfunction "PCIAD20_M34") (pintype "bidirectional+no_connect"))
    )
    (net (code "129") (name "unconnected-(U2H-PCIAD21-PadN31)") (class "Default")
      (node (ref "U2") (pin "N31") (pinfunction "PCIAD21_N31") (pintype "bidirectional+no_connect"))
    )
    (net (code "130") (name "unconnected-(U2H-PCIAD22-PadN33)") (class "Default")
      (node (ref "U2") (pin "N33") (pinfunction "PCIAD22_N33") (pintype "bidirectional+no_connect"))
    )
    (net (code "131") (name "unconnected-(U2H-PCIAD23-PadN32)") (class "Default")
      (node (ref "U2") (pin "N32") (pinfunction "PCIAD23_N32") (pintype "bidirectional+no_connect"))
    )
    (net (code "132") (name "unconnected-(U2H-PCIAD24-PadP31)") (class "Default")
      (node (ref "U2") (pin "P31") (pinfunction "PCIAD24_P31") (pintype "bidirectional+no_connect"))
    )
    (net (code "133") (name "unconnected-(U2H-PCIAD25-PadP33)") (class "Default")
      (node (ref "U2") (pin "P33") (pinfunction "PCIAD25_P33") (pintype "bidirectional+no_connect"))
    )
    (net (code "134") (name "unconnected-(U2H-PCIAD26-PadP32)") (class "Default")
      (node (ref "U2") (pin "P32") (pinfunction "PCIAD26_P32") (pintype "bidirectional+no_connect"))
    )
    (net (code "135") (name "unconnected-(U2H-PCIAD27-PadP34)") (class "Default")
      (node (ref "U2") (pin "P34") (pinfunction "PCIAD27_P34") (pintype "bidirectional+no_connect"))
    )
    (net (code "136") (name "unconnected-(U2H-PCIAD28-PadR31)") (class "Default")
      (node (ref "U2") (pin "R31") (pinfunction "PCIAD28_R31") (pintype "bidirectional+no_connect"))
    )
    (net (code "137") (name "unconnected-(U2H-PCIAD29-PadR32)") (class "Default")
      (node (ref "U2") (pin "R32") (pinfunction "PCIAD29_R32") (pintype "bidirectional+no_connect"))
    )
    (net (code "138") (name "unconnected-(U2H-PCIAD30-PadR33)") (class "Default")
      (node (ref "U2") (pin "R33") (pinfunction "PCIAD30_R33") (pintype "bidirectional+no_connect"))
    )
    (net (code "139") (name "unconnected-(U2H-PCIAD31-PadR34)") (class "Default")
      (node (ref "U2") (pin "R34") (pinfunction "PCIAD31_R34") (pintype "bidirectional+no_connect"))
    )
    (net (code "140") (name "unconnected-(U2H-PCIC0_BE#0-PadG32)") (class "Default")
      (node (ref "U2") (pin "G32") (pinfunction "PCIC0_BE#0_G32") (pintype "bidirectional+no_connect"))
    )
    (net (code "141") (name "unconnected-(U2H-PCIC0_BE#1-PadJ31)") (class "Default")
      (node (ref "U2") (pin "J31") (pinfunction "PCIC0_BE#1_J31") (pintype "bidirectional+no_connect"))
    )
    (net (code "142") (name "unconnected-(U2H-PCIC0_BE#2-PadL34)") (class "Default")
      (node (ref "U2") (pin "L34") (pinfunction "PCIC0_BE#2_L34") (pintype "bidirectional+no_connect"))
    )
    (net (code "143") (name "unconnected-(U2H-PCIC0_BE#3-PadN34)") (class "Default")
      (node (ref "U2") (pin "N34") (pinfunction "PCIC0_BE#3_N34") (pintype "bidirectional+no_connect"))
    )
    (net (code "144") (name "unconnected-(U2H-PCIDEVSEL#-PadK32)") (class "Default")
      (node (ref "U2") (pin "K32") (pinfunction "PCIDEVSEL#_K32") (pintype "bidirectional+no_connect"))
    )
    (net (code "145") (name "unconnected-(U2H-PCIFRAME#-PadL32)") (class "Default")
      (node (ref "U2") (pin "L32") (pinfunction "PCIFRAME#_L32") (pintype "bidirectional+no_connect"))
    )
    (net (code "146") (name "unconnected-(U2H-PCIGNT#0_REQ#-PadY34)") (class "Default")
      (node (ref "U2") (pin "Y34") (pinfunction "PCIGNT#0_REQ#_Y34") (pintype "input+no_connect"))
    )
    (net (code "147") (name "unconnected-(U2H-PCIGNT#1-PadY33)") (class "Default")
      (node (ref "U2") (pin "Y33") (pinfunction "PCIGNT#1_Y33") (pintype "input+no_connect"))
    )
    (net (code "148") (name "unconnected-(U2H-PCIGNT#2-PadY32)") (class "Default")
      (node (ref "U2") (pin "Y32") (pinfunction "PCIGNT#2_Y32") (pintype "input+no_connect"))
    )
    (net (code "149") (name "unconnected-(U2H-PCIGNT#3-PadY31)") (class "Default")
      (node (ref "U2") (pin "Y31") (pinfunction "PCIGNT#3_Y31") (pintype "input+no_connect"))
    )
    (net (code "150") (name "unconnected-(U2H-PCIGNT#4-PadAA33)") (class "Default")
      (node (ref "U2") (pin "AA33") (pinfunction "PCIGNT#4_AA33") (pintype "input+no_connect"))
    )
    (net (code "151") (name "unconnected-(U2H-PCIGNT#5-PadAA34)") (class "Default")
      (node (ref "U2") (pin "AA34") (pinfunction "PCIGNT#5_AA34") (pintype "input+no_connect"))
    )
    (net (code "152") (name "unconnected-(U2H-PCIIDSEL-PadT31)") (class "Default")
      (node (ref "U2") (pin "T31") (pinfunction "PCIIDSEL_T31") (pintype "output+no_connect"))
    )
    (net (code "153") (name "unconnected-(U2H-PCIINT#-PadAB34)") (class "Default")
      (node (ref "U2") (pin "AB34") (pinfunction "PCIINT#_AB34") (pintype "input+no_connect"))
    )
    (net (code "154") (name "unconnected-(U2H-PCIIRDY#-PadK33)") (class "Default")
      (node (ref "U2") (pin "K33") (pinfunction "PCIIRDY#_K33") (pintype "bidirectional+no_connect"))
    )
    (net (code "155") (name "unconnected-(U2H-PCIPAR-PadJ32)") (class "Default")
      (node (ref "U2") (pin "J32") (pinfunction "PCIPAR_J32") (pintype "bidirectional+no_connect"))
    )
    (net (code "156") (name "unconnected-(U2H-PCIPERR#-PadJ33)") (class "Default")
      (node (ref "U2") (pin "J33") (pinfunction "PCIPERR#_J33") (pintype "bidirectional+no_connect"))
    )
    (net (code "157") (name "unconnected-(U2H-PCIRESET#-PadAA31)") (class "Default")
      (node (ref "U2") (pin "AA31") (pinfunction "PCIRESET#_AA31") (pintype "input+no_connect"))
    )
    (net (code "158") (name "unconnected-(U30-NC0-PadA1)") (class "Default")
      (node (ref "U30") (pin "A1") (pinfunction "NC0_A1") (pintype "tri_state+no_connect"))
    )
    (net (code "159") (name "unconnected-(U30-NC1-PadC1)") (class "Default")
      (node (ref "U30") (pin "C1") (pinfunction "NC1_C1") (pintype "tri_state+no_connect"))
    )
    (net (code "160") (name "unconnected-(U30-NC2-PadD1)") (class "Default")
      (node (ref "U30") (pin "D1") (pinfunction "NC2_D1") (pintype "tri_state+no_connect"))
    )
    (net (code "161") (name "unconnected-(U30-NC3-PadE1)") (class "Default")
      (node (ref "U30") (pin "E1") (pinfunction "NC3_E1") (pintype "tri_state+no_connect"))
    )
    (net (code "162") (name "unconnected-(U30-NC4-PadG1)") (class "Default")
      (node (ref "U30") (pin "G1") (pinfunction "NC4_G1") (pintype "tri_state+no_connect"))
    )
    (net (code "163") (name "unconnected-(U30-NC5-PadH1)") (class "Default")
      (node (ref "U30") (pin "H1") (pinfunction "NC5_H1") (pintype "tri_state+no_connect"))
    )
    (net (code "164") (name "unconnected-(U30-NC6-PadA8)") (class "Default")
      (node (ref "U30") (pin "A8") (pinfunction "NC6_A8") (pintype "tri_state+no_connect"))
    )
    (net (code "165") (name "unconnected-(U30-NC7-PadH8)") (class "Default")
      (node (ref "U30") (pin "H8") (pinfunction "NC7_H8") (pintype "tri_state+no_connect"))
    )
  )
)
